# 5_-_Status_Lights.net
KiCad netlist of a schematic drawn in Altium Designer
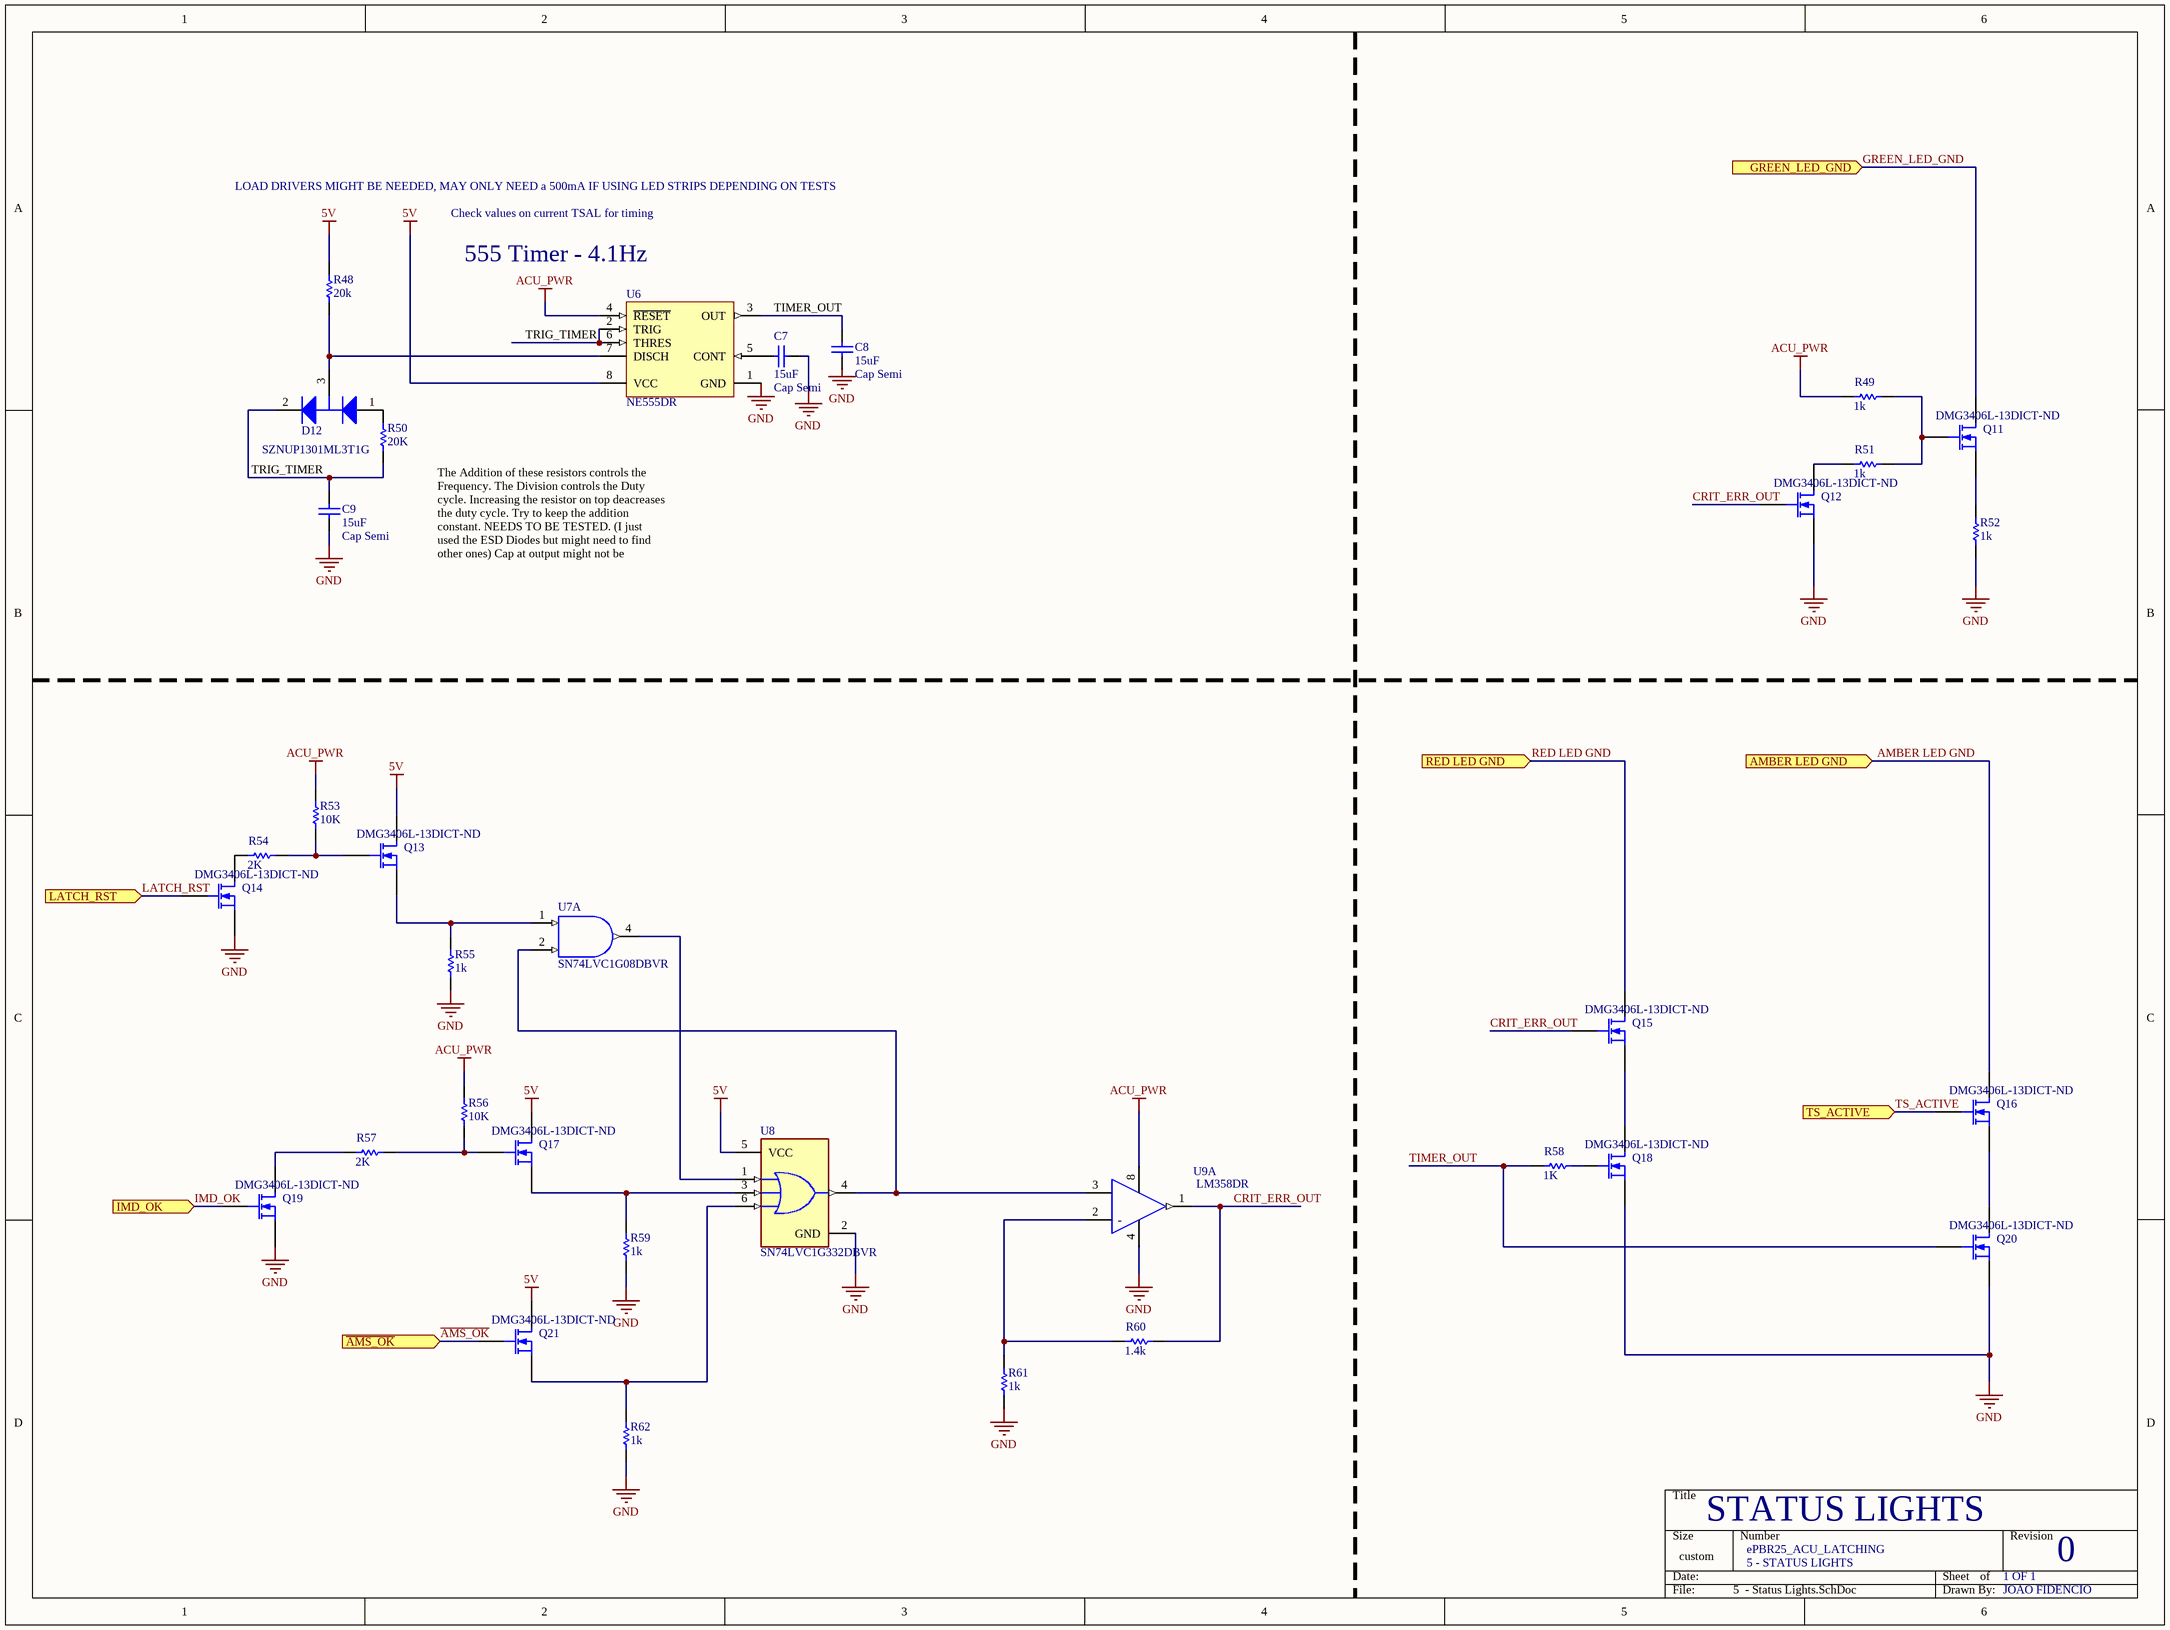
[diagram p0: 5  - Status Lights.SchDoc]

(export (version "E")
  (design (tool "Eeschema 10.0.6"))
  (components
    (comp (ref "C7")
      (value "Cap Semi")
      (footprint "1608[0603]")
      (description "Capacitor (Semiconductor SIM Model)")
      (fields (field (name "ALTIUM_VALUE") "15uF") (field (name "PUBLISHER") "Altium Limited"))
      (libsource (lib "Miscellaneous Devices") (part "Cap Semi"))
    )
    (comp (ref "C8")
      (value "Cap Semi")
      (footprint "1608[0603]")
      (description "Capacitor (Semiconductor SIM Model)")
      (fields (field (name "ALTIUM_VALUE") "15uF") (field (name "PUBLISHER") "Altium Limited"))
      (libsource (lib "Miscellaneous Devices") (part "Cap Semi"))
    )
    (comp (ref "C9")
      (value "Cap Semi")
      (footprint "1608[0603]")
      (description "Capacitor (Semiconductor SIM Model)")
      (fields (field (name "ALTIUM_VALUE") "15uF") (field (name "PUBLISHER") "Altium Limited"))
      (libsource (lib "Miscellaneous Devices") (part "Cap Semi"))
    )
    (comp (ref "D12")
      (value "SZNUP1301ML3T1G")
      (footprint "ONSC-SOT-23-3-318-08_V")
      (fields (field (name "MANUFACTURER") "On Semiconductor"))
      (libsource (lib "Altium Content Vault") (part "ONSC-NUP1301-SOT-23-3-318-08"))
    )
    (comp (ref "Q11")
      (value "~")
      (footprint "SOT23-GDS")
      (description "N-Channel MOSFET")
      (fields
        (field (name "MANUFACTURER") "Infineon Technologies")
        (field (name "SUPPLIER PART NUMBER 1") "DMG3406L-13DICT-ND")
        (field (name "PUBLISHER") "Altium Limited")
      )
      (libsource (lib "Miscellaneous Devices") (part "MOSFET-N"))
    )
    (comp (ref "Q12")
      (value "~")
      (footprint "SOT23-GDS")
      (description "N-Channel MOSFET")
      (fields
        (field (name "MANUFACTURER") "Infineon Technologies")
        (field (name "SUPPLIER PART NUMBER 1") "DMG3406L-13DICT-ND")
        (field (name "PUBLISHER") "Altium Limited")
      )
      (libsource (lib "Miscellaneous Devices") (part "MOSFET-N"))
    )
    (comp (ref "Q13")
      (value "~")
      (footprint "SOT23-GDS")
      (description "N-Channel MOSFET")
      (fields
        (field (name "MANUFACTURER") "Infineon Technologies")
        (field (name "SUPPLIER PART NUMBER 1") "DMG3406L-13DICT-ND")
        (field (name "PUBLISHER") "Altium Limited")
      )
      (libsource (lib "Miscellaneous Devices") (part "MOSFET-N"))
    )
    (comp (ref "Q14")
      (value "~")
      (footprint "SOT23-GDS")
      (description "N-Channel MOSFET")
      (fields
        (field (name "MANUFACTURER") "Infineon Technologies")
        (field (name "SUPPLIER PART NUMBER 1") "DMG3406L-13DICT-ND")
        (field (name "PUBLISHER") "Altium Limited")
      )
      (libsource (lib "Miscellaneous Devices") (part "MOSFET-N"))
    )
    (comp (ref "Q15")
      (value "~")
      (footprint "SOT23-GDS")
      (description "N-Channel MOSFET")
      (fields
        (field (name "MANUFACTURER") "Infineon Technologies")
        (field (name "SUPPLIER PART NUMBER 1") "DMG3406L-13DICT-ND")
        (field (name "PUBLISHER") "Altium Limited")
      )
      (libsource (lib "Miscellaneous Devices") (part "MOSFET-N"))
    )
    (comp (ref "Q16")
      (value "~")
      (footprint "SOT23-GDS")
      (description "N-Channel MOSFET")
      (fields
        (field (name "MANUFACTURER") "Infineon Technologies")
        (field (name "SUPPLIER PART NUMBER 1") "DMG3406L-13DICT-ND")
        (field (name "PUBLISHER") "Altium Limited")
      )
      (libsource (lib "Miscellaneous Devices") (part "MOSFET-N"))
    )
    (comp (ref "Q17")
      (value "~")
      (footprint "SOT23-GDS")
      (description "N-Channel MOSFET")
      (fields
        (field (name "MANUFACTURER") "Infineon Technologies")
        (field (name "SUPPLIER PART NUMBER 1") "DMG3406L-13DICT-ND")
        (field (name "PUBLISHER") "Altium Limited")
      )
      (libsource (lib "Miscellaneous Devices") (part "MOSFET-N"))
    )
    (comp (ref "Q18")
      (value "~")
      (footprint "SOT23-GDS")
      (description "N-Channel MOSFET")
      (fields
        (field (name "MANUFACTURER") "Infineon Technologies")
        (field (name "SUPPLIER PART NUMBER 1") "DMG3406L-13DICT-ND")
        (field (name "PUBLISHER") "Altium Limited")
      )
      (libsource (lib "Miscellaneous Devices") (part "MOSFET-N"))
    )
    (comp (ref "Q19")
      (value "~")
      (footprint "SOT23-GDS")
      (description "N-Channel MOSFET")
      (fields
        (field (name "MANUFACTURER") "Infineon Technologies")
        (field (name "SUPPLIER PART NUMBER 1") "DMG3406L-13DICT-ND")
        (field (name "PUBLISHER") "Altium Limited")
      )
      (libsource (lib "Miscellaneous Devices") (part "MOSFET-N"))
    )
    (comp (ref "Q20")
      (value "~")
      (footprint "SOT23-GDS")
      (description "N-Channel MOSFET")
      (fields
        (field (name "MANUFACTURER") "Infineon Technologies")
        (field (name "SUPPLIER PART NUMBER 1") "DMG3406L-13DICT-ND")
        (field (name "PUBLISHER") "Altium Limited")
      )
      (libsource (lib "Miscellaneous Devices") (part "MOSFET-N"))
    )
    (comp (ref "Q21")
      (value "~")
      (footprint "SOT23-GDS")
      (description "N-Channel MOSFET")
      (fields
        (field (name "MANUFACTURER") "Infineon Technologies")
        (field (name "SUPPLIER PART NUMBER 1") "DMG3406L-13DICT-ND")
        (field (name "PUBLISHER") "Altium Limited")
      )
      (libsource (lib "Miscellaneous Devices") (part "MOSFET-N"))
    )
    (comp (ref "R48")
      (value "20k")
      (footprint "RESC0603(1608)_L")
      (description "0603 (1608 Metric) Chip Resistor")
      (libsource (lib "Altium Content Vault") (part "RES_3"))
    )
    (comp (ref "R49")
      (value "1k")
      (footprint "RESC0603(1608)_L")
      (description "0603 (1608 Metric) Chip Resistor")
      (libsource (lib "Altium Content Vault") (part "RES_3"))
    )
    (comp (ref "R50")
      (value "20K")
      (footprint "RESC0603(1608)_L")
      (description "0603 (1608 Metric) Chip Resistor")
      (libsource (lib "Altium Content Vault") (part "RES_3"))
    )
    (comp (ref "R51")
      (value "1k")
      (footprint "RESC0603(1608)_L")
      (description "0603 (1608 Metric) Chip Resistor")
      (libsource (lib "Altium Content Vault") (part "RES_3"))
    )
    (comp (ref "R52")
      (value "1k")
      (footprint "RESC0603(1608)_L")
      (description "0603 (1608 Metric) Chip Resistor")
      (libsource (lib "Altium Content Vault") (part "RES_3"))
    )
    (comp (ref "R53")
      (value "10K")
      (footprint "RESC0603(1608)_L")
      (description "0603 (1608 Metric) Chip Resistor")
      (libsource (lib "Altium Content Vault") (part "RES_3"))
    )
    (comp (ref "R54")
      (value "2K")
      (footprint "RESC0603(1608)_L")
      (description "0603 (1608 Metric) Chip Resistor")
      (libsource (lib "Altium Content Vault") (part "RES_3"))
    )
    (comp (ref "R55")
      (value "1k")
      (footprint "RESC0603(1608)_L")
      (description "0603 (1608 Metric) Chip Resistor")
      (libsource (lib "Altium Content Vault") (part "RES_3"))
    )
    (comp (ref "R56")
      (value "10K")
      (footprint "RESC0603(1608)_L")
      (description "0603 (1608 Metric) Chip Resistor")
      (libsource (lib "Altium Content Vault") (part "RES_3"))
    )
    (comp (ref "R57")
      (value "2K")
      (footprint "RESC0603(1608)_L")
      (description "0603 (1608 Metric) Chip Resistor")
      (libsource (lib "Altium Content Vault") (part "RES_3"))
    )
    (comp (ref "R58")
      (value "1K")
      (footprint "RESC0603(1608)_L")
      (description "0603 (1608 Metric) Chip Resistor")
      (libsource (lib "Altium Content Vault") (part "RES_3"))
    )
    (comp (ref "R59")
      (value "1k")
      (footprint "RESC0603(1608)_L")
      (description "0603 (1608 Metric) Chip Resistor")
      (libsource (lib "Altium Content Vault") (part "RES_3"))
    )
    (comp (ref "R60")
      (value "1.4k")
      (footprint "RESC0603(1608)_L")
      (description "0603 (1608 Metric) Chip Resistor")
      (libsource (lib "Altium Content Vault") (part "RES_3"))
    )
    (comp (ref "R61")
      (value "1k")
      (footprint "RESC0603(1608)_L")
      (description "0603 (1608 Metric) Chip Resistor")
      (libsource (lib "Altium Content Vault") (part "RES_3"))
    )
    (comp (ref "R62")
      (value "1k")
      (footprint "RESC0603(1608)_L")
      (description "0603 (1608 Metric) Chip Resistor")
      (libsource (lib "Altium Content Vault") (part "RES_3"))
    )
    (comp (ref "U6")
      (value "NE555DR")
      (footprint "D0008A_M")
      (libsource (lib "Altium Content Vault") (part "CMP-1685-00007-1"))
    )
    (comp (ref "U7")
      (value "SN74LVC1G08DBVR")
      (footprint "DBV0005A_M")
      (description "Single 2-Input Positive-AND Gate, DBV0005A, LARGE T&R")
      (fields
        (field (name "GENERIC PART NUMBER") "SN74LVC1G08")
        (field (name "MANUFACTURER") "Texas Instruments")
      )
      (libsource (lib "Altium Content Vault") (part "TI-SN74XXX1X08-5"))
    )
    (comp (ref "U8")
      (value "SN74LVC1G332DBVR")
      (footprint "FP-DBV0006A-MFG")
      (description "IC GATE OR 1CH 3-INP SOT23-6")
      (fields
        (field (name "OCTOPART") "https://octopart.com/sn74lvc1g332dbvr-texas+instruments-464996")
        (field (name "MANUFACTURER") "TEXAS INSTRUMENTS")
      )
      (libsource (lib "Altium Content Vault") (part "9bd6587d4ded7f3f3ab4f7d0d680d6b"))
    )
    (comp (ref "U9")
      (value "LM358DR")
      (footprint "FP-D0008A-MFG")
      (description "IC OPAMP GP 2 CIRCUIT 8SOIC")
      (libsource (lib "Altium Content Vault") (part "0afdfe5f461d2cdd85604ff8654be97"))
    )
  )
  (nets
    (net (code "1") (name "/AMBER LED GND") (class "Default")
      (node (ref "Q16") (pin "3") (pinfunction "D_3") (pintype "passive"))
    )
    (net (code "2") (name "/CRIT_ERR_OUT") (class "Default")
      (node (ref "Q12") (pin "1") (pinfunction "G_1") (pintype "passive"))
      (node (ref "Q15") (pin "1") (pinfunction "G_1") (pintype "passive"))
      (node (ref "R60") (pin "2") (pinfunction "2_2") (pintype "passive"))
      (node (ref "U9") (pin "1") (pinfunction "1OUT_1") (pintype "output"))
    )
    (net (code "3") (name "/GREEN_LED_GND") (class "Default")
      (node (ref "Q11") (pin "3") (pinfunction "D_3") (pintype "passive"))
    )
    (net (code "4") (name "/IMD_OK") (class "Default")
      (node (ref "Q19") (pin "1") (pinfunction "G_1") (pintype "passive"))
    )
    (net (code "5") (name "/LATCH_RST") (class "Default")
      (node (ref "Q14") (pin "1") (pinfunction "G_1") (pintype "passive"))
    )
    (net (code "6") (name "/RED LED GND") (class "Default")
      (node (ref "Q15") (pin "3") (pinfunction "D_3") (pintype "passive"))
    )
    (net (code "7") (name "/TIMER_OUT") (class "Default")
      (node (ref "C8") (pin "1") (pinfunction "1_1") (pintype "passive"))
      (node (ref "Q20") (pin "1") (pinfunction "G_1") (pintype "passive"))
      (node (ref "R58") (pin "1") (pinfunction "1_1") (pintype "passive"))
      (node (ref "U6") (pin "3") (pinfunction "OUT_3") (pintype "output"))
    )
    (net (code "8") (name "/TRIG_TIMER") (class "Default")
      (node (ref "C9") (pin "1") (pinfunction "1_1") (pintype "passive"))
      (node (ref "D12") (pin "2") (pinfunction "K_2") (pintype "passive"))
      (node (ref "R50") (pin "1") (pinfunction "1_1") (pintype "passive"))
      (node (ref "U6") (pin "2") (pinfunction "TRIG_2") (pintype "input"))
      (node (ref "U6") (pin "6") (pinfunction "THRES_6") (pintype "input"))
    )
    (net (code "9") (name "/TS_ACTIVE") (class "Default")
      (node (ref "Q16") (pin "1") (pinfunction "G_1") (pintype "passive"))
    )
    (net (code "10") (name "/~{AMS_OK}") (class "Default")
      (node (ref "Q21") (pin "1") (pinfunction "G_1") (pintype "passive"))
    )
    (net (code "11") (name "5V") (class "Default")
      (node (ref "Q13") (pin "3") (pinfunction "D_3") (pintype "passive"))
      (node (ref "Q17") (pin "3") (pinfunction "D_3") (pintype "passive"))
      (node (ref "Q21") (pin "3") (pinfunction "D_3") (pintype "passive"))
      (node (ref "R48") (pin "1") (pinfunction "1_1") (pintype "passive"))
      (node (ref "U6") (pin "8") (pinfunction "VCC_8") (pintype "power_in"))
      (node (ref "U8") (pin "5") (pinfunction "VCC_5") (pintype "power_in"))
    )
    (net (code "12") (name "ACU_PWR") (class "Default")
      (node (ref "R49") (pin "1") (pinfunction "1_1") (pintype "passive"))
      (node (ref "R53") (pin "2") (pinfunction "2_2") (pintype "passive"))
      (node (ref "R56") (pin "2") (pinfunction "2_2") (pintype "passive"))
      (node (ref "U6") (pin "4") (pinfunction "~{RESET}_4") (pintype "input"))
      (node (ref "U9") (pin "8") (pinfunction "V+_8") (pintype "power_in"))
    )
    (net (code "13") (name "GND") (class "Default")
      (node (ref "C7") (pin "1") (pinfunction "1_1") (pintype "passive"))
      (node (ref "C9") (pin "2") (pinfunction "2_2") (pintype "passive"))
      (node (ref "Q12") (pin "2") (pinfunction "S_2") (pintype "passive"))
      (node (ref "Q14") (pin "2") (pinfunction "S_2") (pintype "passive"))
      (node (ref "Q18") (pin "2") (pinfunction "S_2") (pintype "passive"))
      (node (ref "Q19") (pin "2") (pinfunction "S_2") (pintype "passive"))
      (node (ref "Q20") (pin "2") (pinfunction "S_2") (pintype "passive"))
      (node (ref "R52") (pin "1") (pinfunction "1_1") (pintype "passive"))
      (node (ref "R55") (pin "2") (pinfunction "2_2") (pintype "passive"))
      (node (ref "R59") (pin "2") (pinfunction "2_2") (pintype "passive"))
      (node (ref "R61") (pin "2") (pinfunction "2_2") (pintype "passive"))
      (node (ref "R62") (pin "2") (pinfunction "2_2") (pintype "passive"))
      (node (ref "U6") (pin "1") (pinfunction "GND_1") (pintype "power_in"))
      (node (ref "U8") (pin "2") (pinfunction "GND_2") (pintype "power_in"))
      (node (ref "U9") (pin "4") (pinfunction "V-_4") (pintype "power_in"))
    )
    (net (code "14") (name "Net-(D12-A)") (class "Default")
      (node (ref "D12") (pin "1") (pinfunction "A_1") (pintype "passive"))
      (node (ref "R50") (pin "2") (pinfunction "2_2") (pintype "passive"))
    )
    (net (code "15") (name "Net-(D12-K{slash}A)") (class "Default")
      (node (ref "D12") (pin "3") (pinfunction "K/A_3") (pintype "passive"))
      (node (ref "R48") (pin "2") (pinfunction "2_2") (pintype "passive"))
      (node (ref "U6") (pin "7") (pinfunction "DISCH_7") (pintype "open_collector"))
    )
    (net (code "16") (name "Net-(Q11-G)") (class "Default")
      (node (ref "Q11") (pin "1") (pinfunction "G_1") (pintype "passive"))
      (node (ref "R49") (pin "2") (pinfunction "2_2") (pintype "passive"))
      (node (ref "R51") (pin "2") (pinfunction "2_2") (pintype "passive"))
    )
    (net (code "17") (name "Net-(Q11-S)") (class "Default")
      (node (ref "Q11") (pin "2") (pinfunction "S_2") (pintype "passive"))
      (node (ref "R52") (pin "2") (pinfunction "2_2") (pintype "passive"))
    )
    (net (code "18") (name "Net-(Q12-D)") (class "Default")
      (node (ref "Q12") (pin "3") (pinfunction "D_3") (pintype "passive"))
      (node (ref "R51") (pin "1") (pinfunction "1_1") (pintype "passive"))
    )
    (net (code "19") (name "Net-(Q13-G)") (class "Default")
      (node (ref "Q13") (pin "1") (pinfunction "G_1") (pintype "passive"))
      (node (ref "R53") (pin "1") (pinfunction "1_1") (pintype "passive"))
      (node (ref "R54") (pin "2") (pinfunction "2_2") (pintype "passive"))
    )
    (net (code "20") (name "Net-(Q13-S)") (class "Default")
      (node (ref "Q13") (pin "2") (pinfunction "S_2") (pintype "passive"))
      (node (ref "R55") (pin "1") (pinfunction "1_1") (pintype "passive"))
      (node (ref "U7") (pin "1") (pinfunction "A_1") (pintype "input"))
    )
    (net (code "21") (name "Net-(Q14-D)") (class "Default")
      (node (ref "Q14") (pin "3") (pinfunction "D_3") (pintype "passive"))
      (node (ref "R54") (pin "1") (pinfunction "1_1") (pintype "passive"))
    )
    (net (code "22") (name "Net-(Q15-S)") (class "Default")
      (node (ref "Q15") (pin "2") (pinfunction "S_2") (pintype "passive"))
      (node (ref "Q18") (pin "3") (pinfunction "D_3") (pintype "passive"))
    )
    (net (code "23") (name "Net-(Q16-S)") (class "Default")
      (node (ref "Q16") (pin "2") (pinfunction "S_2") (pintype "passive"))
      (node (ref "Q20") (pin "3") (pinfunction "D_3") (pintype "passive"))
    )
    (net (code "24") (name "Net-(Q17-G)") (class "Default")
      (node (ref "Q17") (pin "1") (pinfunction "G_1") (pintype "passive"))
      (node (ref "R56") (pin "1") (pinfunction "1_1") (pintype "passive"))
      (node (ref "R57") (pin "2") (pinfunction "2_2") (pintype "passive"))
    )
    (net (code "25") (name "Net-(Q17-S)") (class "Default")
      (node (ref "Q17") (pin "2") (pinfunction "S_2") (pintype "passive"))
      (node (ref "R59") (pin "1") (pinfunction "1_1") (pintype "passive"))
      (node (ref "U8") (pin "3") (pinfunction "B_3") (pintype "input"))
    )
    (net (code "26") (name "Net-(Q18-G)") (class "Default")
      (node (ref "Q18") (pin "1") (pinfunction "G_1") (pintype "passive"))
      (node (ref "R58") (pin "2") (pinfunction "2_2") (pintype "passive"))
    )
    (net (code "27") (name "Net-(Q19-D)") (class "Default")
      (node (ref "Q19") (pin "3") (pinfunction "D_3") (pintype "passive"))
      (node (ref "R57") (pin "1") (pinfunction "1_1") (pintype "passive"))
    )
    (net (code "28") (name "Net-(Q21-S)") (class "Default")
      (node (ref "Q21") (pin "2") (pinfunction "S_2") (pintype "passive"))
      (node (ref "R62") (pin "1") (pinfunction "1_1") (pintype "passive"))
      (node (ref "U8") (pin "6") (pinfunction "C_6") (pintype "input"))
    )
    (net (code "29") (name "Net-(U6-CONT)") (class "Default")
      (node (ref "C7") (pin "2") (pinfunction "2_2") (pintype "passive"))
      (node (ref "U6") (pin "5") (pinfunction "CONT_5") (pintype "input"))
    )
    (net (code "30") (name "Net-(U7A-B)") (class "Default")
      (node (ref "U7") (pin "2") (pinfunction "B_2") (pintype "input"))
      (node (ref "U8") (pin "4") (pinfunction "Y_4") (pintype "output"))
      (node (ref "U9") (pin "3") (pinfunction "IN1+_3") (pintype "tri_state"))
    )
    (net (code "31") (name "Net-(U7A-Y)") (class "Default")
      (node (ref "U7") (pin "4") (pinfunction "Y_4") (pintype "output"))
      (node (ref "U8") (pin "1") (pinfunction "A_1") (pintype "input"))
    )
    (net (code "32") (name "Net-(U9A-IN1-)") (class "Default")
      (node (ref "R60") (pin "1") (pinfunction "1_1") (pintype "passive"))
      (node (ref "R61") (pin "1") (pinfunction "1_1") (pintype "passive"))
      (node (ref "U9") (pin "2") (pinfunction "IN1-_2") (pintype "tri_state"))
    )
    (net (code "33") (name "unconnected-(C8-Pad2)") (class "Default")
      (node (ref "C8") (pin "2") (pinfunction "2_2") (pintype "passive"))
    )
  )
)
